# SparkFun_Cryptographic_Co-processor_ATEC.net
KiCad netlist of a schematic drawn in EAGLE
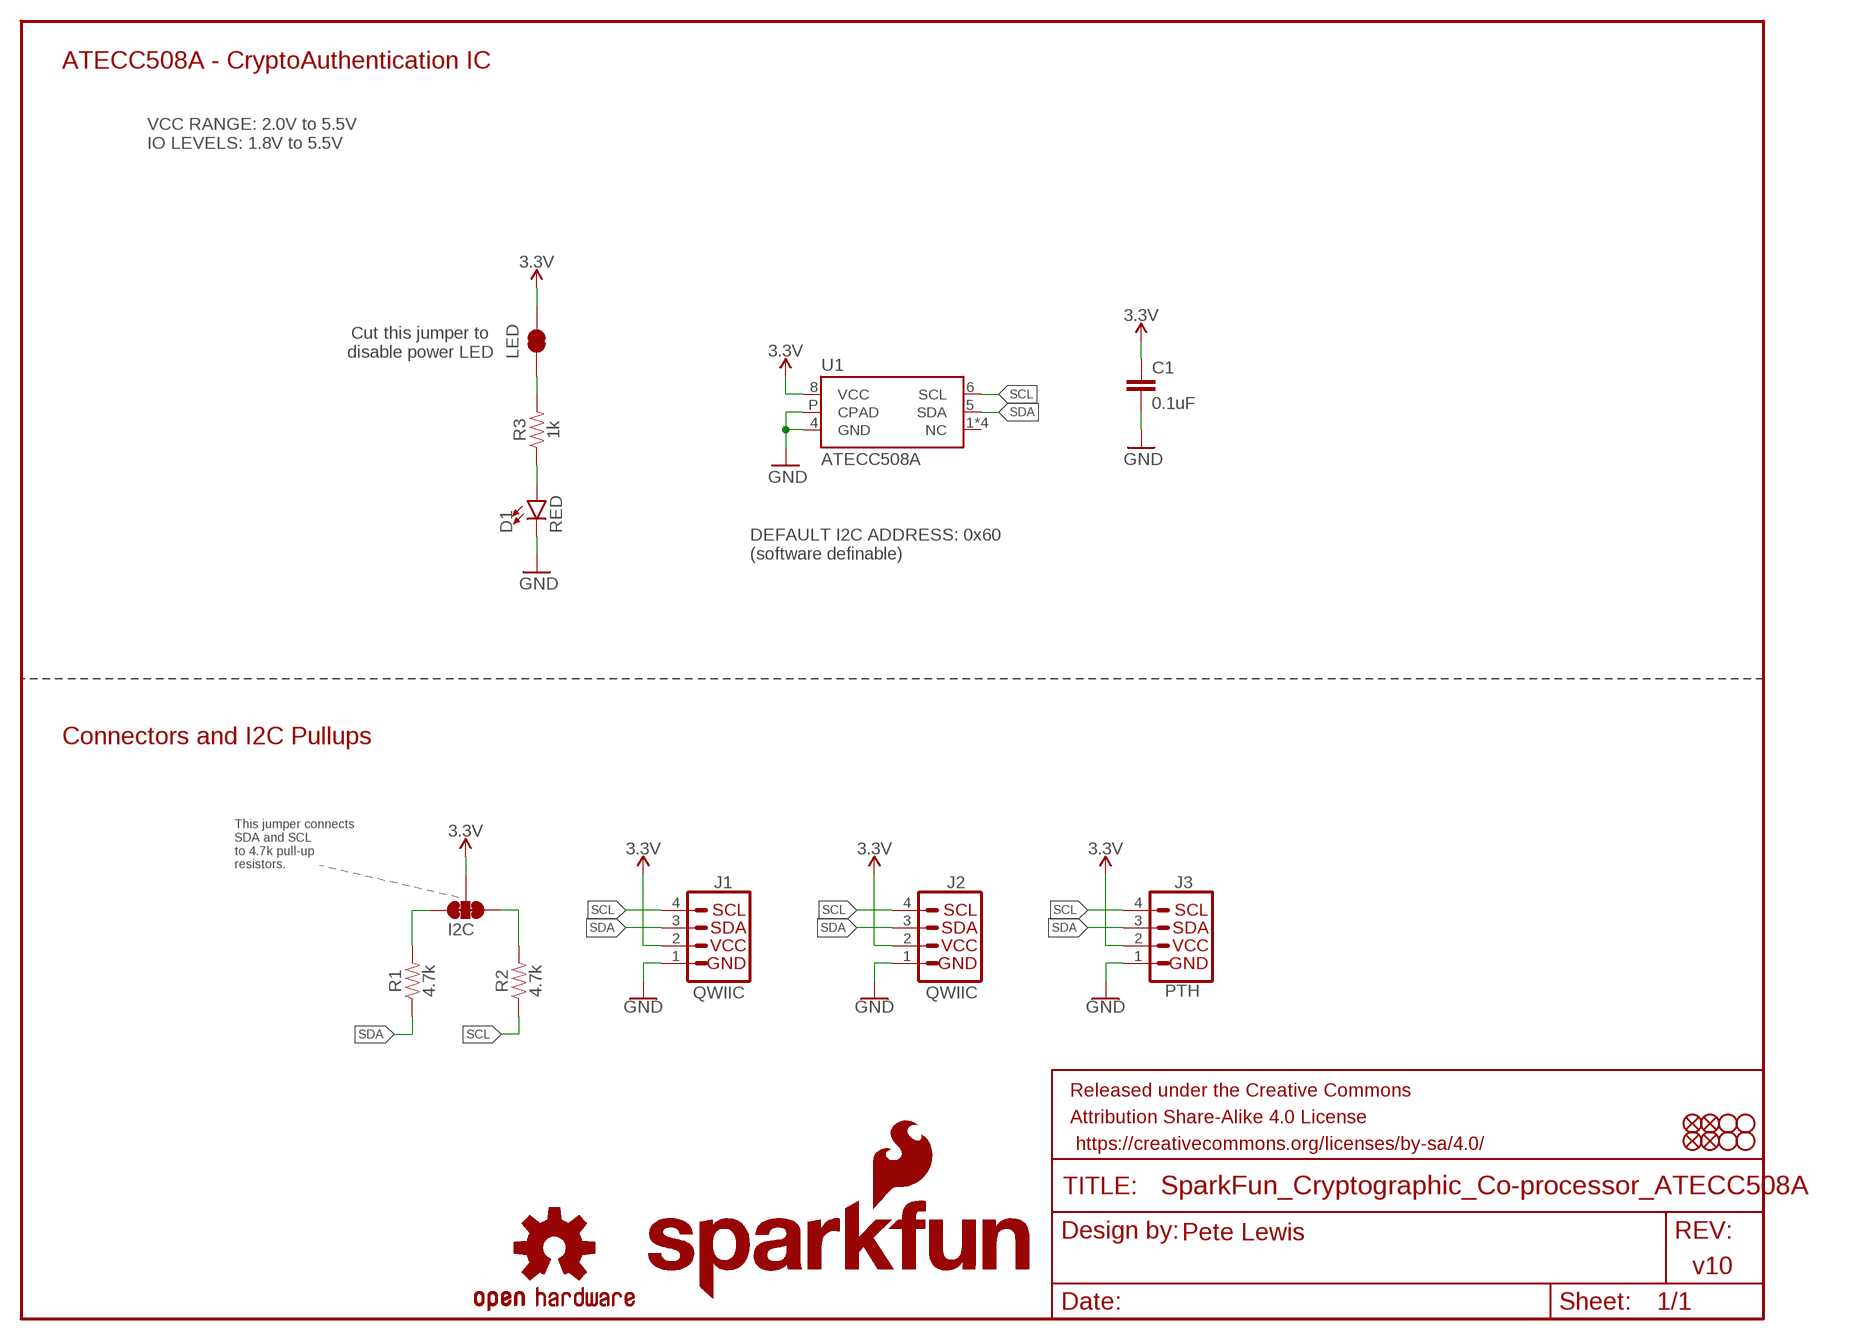
[diagram p0: schematic, sheet 1]

(export (version "E")
  (design (tool "Eeschema 10.0.6"))
  (components
    (comp (ref "C1")
      (value "0.1uF")
      (footprint "eagle-import:0603")
      (libsource (lib "eagle-import") (part "0.1UF-0603-25V-(+80/-20%)"))
    )
    (comp (ref "D1")
      (value "RED")
      (footprint "eagle-import:LED-0603")
      (libsource (lib "eagle-import") (part "LED-RED0603"))
    )
    (comp (ref "FD1")
      (value "FIDUCIAL1X2")
      (footprint "eagle-import:FIDUCIAL-1X2")
      (libsource (lib "eagle-import") (part "FIDUCIAL1X2"))
    )
    (comp (ref "FD2")
      (value "FIDUCIAL1X2")
      (footprint "eagle-import:FIDUCIAL-1X2")
      (libsource (lib "eagle-import") (part "FIDUCIAL1X2"))
    )
    (comp (ref "FD3")
      (value "FIDUCIAL1X2")
      (footprint "eagle-import:FIDUCIAL-1X2")
      (libsource (lib "eagle-import") (part "FIDUCIAL1X2"))
    )
    (comp (ref "FD4")
      (value "FIDUCIAL1X2")
      (footprint "eagle-import:FIDUCIAL-1X2")
      (libsource (lib "eagle-import") (part "FIDUCIAL1X2"))
    )
    (comp (ref "FRAME1")
      (value "FRAME-LETTER")
      (footprint "eagle-import:CREATIVE_COMMONS")
      (libsource (lib "eagle-import") (part "FRAME-LETTER"))
    )
    (comp (ref "H1")
      (value "STAND-OFF")
      (footprint "eagle-import:STAND-OFF")
      (libsource (lib "eagle-import") (part "STAND-OFF"))
    )
    (comp (ref "H2")
      (value "STAND-OFF")
      (footprint "eagle-import:STAND-OFF")
      (libsource (lib "eagle-import") (part "STAND-OFF"))
    )
    (comp (ref "H3")
      (value "STAND-OFF")
      (footprint "eagle-import:STAND-OFF")
      (libsource (lib "eagle-import") (part "STAND-OFF"))
    )
    (comp (ref "H4")
      (value "STAND-OFF")
      (footprint "eagle-import:STAND-OFF")
      (libsource (lib "eagle-import") (part "STAND-OFF"))
    )
    (comp (ref "I2C")
      (value "JUMPER-SMT_3_2-NC_TRACE_SILK")
      (footprint "eagle-import:SMT-JUMPER_3_2-NC_TRACE_SILK")
      (libsource (lib "eagle-import") (part "JUMPER-SMT_3_2-NC_TRACE_SILK"))
    )
    (comp (ref "J1")
      (value "QWIIC")
      (footprint "eagle-import:JST04_1MM_RA")
      (libsource (lib "eagle-import") (part "I2C_STANDARDQWIIC"))
    )
    (comp (ref "J2")
      (value "QWIIC")
      (footprint "eagle-import:JST04_1MM_RA")
      (libsource (lib "eagle-import") (part "I2C_STANDARDQWIIC"))
    )
    (comp (ref "J3")
      (value "PTH")
      (footprint "eagle-import:1X04_NO_SILK")
      (libsource (lib "eagle-import") (part "I2C_STANDARD_NO_SILK"))
    )
    (comp (ref "LED")
      (value "JUMPER-SMT_2_NC_TRACE_SILK")
      (footprint "eagle-import:SMT-JUMPER_2_NC_TRACE_SILK")
      (libsource (lib "eagle-import") (part "JUMPER-SMT_2_NC_TRACE_SILK"))
    )
    (comp (ref "LOGO1")
      (value "SFE_LOGO_NAME_FLAME.1_INCH")
      (footprint "eagle-import:SFE_LOGO_NAME_FLAME_.1")
      (libsource (lib "eagle-import") (part "SFE_LOGO_NAME_FLAME.1_INCH"))
    )
    (comp (ref "LOGO4")
      (value "OSHW-LOGOS")
      (footprint "eagle-import:OSHW-LOGO-S")
      (libsource (lib "eagle-import") (part "OSHW-LOGOS"))
    )
    (comp (ref "R1")
      (value "4.7k")
      (footprint "eagle-import:0603")
      (libsource (lib "eagle-import") (part "4.7KOHM-0603-1/10W-1%"))
    )
    (comp (ref "R2")
      (value "4.7k")
      (footprint "eagle-import:0603")
      (libsource (lib "eagle-import") (part "4.7KOHM-0603-1/10W-1%"))
    )
    (comp (ref "R3")
      (value "1k")
      (footprint "eagle-import:0603")
      (libsource (lib "eagle-import") (part "1KOHM-0603-1/10W-1%"))
    )
    (comp (ref "U1")
      (value "ATECC508A")
      (footprint "eagle-import:UDFN_2X3MM")
      (libsource (lib "eagle-import") (part "ATECC508AUDFN_2X3MM"))
    )
  )
  (nets
    (net (code "1") (name "3.3V") (class "Default")
      (node (ref "C1") (pin "1") (pinfunction "1_1") (pintype "passive"))
      (node (ref "I2C") (pin "2") (pinfunction "2_2") (pintype "passive"))
      (node (ref "J1") (pin "2") (pinfunction "2_2") (pintype "power_in"))
      (node (ref "J2") (pin "2") (pinfunction "2_2") (pintype "power_in"))
      (node (ref "J3") (pin "2") (pinfunction "2_2") (pintype "power_in"))
      (node (ref "LED") (pin "2") (pinfunction "2_2") (pintype "passive"))
      (node (ref "U1") (pin "8") (pinfunction "VCC_8") (pintype "power_in"))
    )
    (net (code "2") (name "GND") (class "Default")
      (node (ref "C1") (pin "2") (pinfunction "2_2") (pintype "passive"))
      (node (ref "D1") (pin "C") (pinfunction "C_C") (pintype "passive"))
      (node (ref "J1") (pin "1") (pinfunction "1_1") (pintype "power_in"))
      (node (ref "J2") (pin "1") (pinfunction "1_1") (pintype "power_in"))
      (node (ref "J3") (pin "1") (pinfunction "1_1") (pintype "power_in"))
      (node (ref "U1") (pin "4") (pinfunction "GND_4") (pintype "power_in"))
      (node (ref "U1") (pin "P") (pinfunction "CPAD_P") (pintype "power_in"))
    )
    (net (code "3") (name "Net-(D1-PadA)") (class "Default")
      (node (ref "D1") (pin "A") (pinfunction "A_A") (pintype "passive"))
      (node (ref "R3") (pin "1") (pinfunction "1_1") (pintype "passive"))
    )
    (net (code "4") (name "Net-(I2C-Pad1)") (class "Default")
      (node (ref "I2C") (pin "1") (pinfunction "1_1") (pintype "passive"))
      (node (ref "R2") (pin "2") (pinfunction "2_2") (pintype "passive"))
    )
    (net (code "5") (name "Net-(I2C-Pad3)") (class "Default")
      (node (ref "I2C") (pin "3") (pinfunction "3_3") (pintype "passive"))
      (node (ref "R1") (pin "2") (pinfunction "2_2") (pintype "passive"))
    )
    (net (code "6") (name "Net-(LED-Pad1)") (class "Default")
      (node (ref "LED") (pin "1") (pinfunction "1_1") (pintype "passive"))
      (node (ref "R3") (pin "2") (pinfunction "2_2") (pintype "passive"))
    )
    (net (code "7") (name "SCL") (class "Default")
      (node (ref "J1") (pin "4") (pinfunction "4_4") (pintype "passive"))
      (node (ref "J2") (pin "4") (pinfunction "4_4") (pintype "passive"))
      (node (ref "J3") (pin "4") (pinfunction "4_4") (pintype "passive"))
      (node (ref "R2") (pin "1") (pinfunction "1_1") (pintype "passive"))
      (node (ref "U1") (pin "6") (pinfunction "SCL_6") (pintype "bidirectional"))
    )
    (net (code "8") (name "SDA") (class "Default")
      (node (ref "J1") (pin "3") (pinfunction "3_3") (pintype "passive"))
      (node (ref "J2") (pin "3") (pinfunction "3_3") (pintype "passive"))
      (node (ref "J3") (pin "3") (pinfunction "3_3") (pintype "passive"))
      (node (ref "R1") (pin "1") (pinfunction "1_1") (pintype "passive"))
      (node (ref "U1") (pin "5") (pinfunction "SDA_5") (pintype "bidirectional"))
    )
    (net (code "9") (name "unconnected-(U1-NC-Pad1)") (class "Default")
      (node (ref "U1") (pin "1") (pinfunction "NC_1") (pintype "no_connect"))
    )
    (net (code "10") (name "unconnected-(U1-NC-Pad2)") (class "Default")
      (node (ref "U1") (pin "2") (pinfunction "NC_2") (pintype "no_connect"))
    )
    (net (code "11") (name "unconnected-(U1-NC-Pad3)") (class "Default")
      (node (ref "U1") (pin "3") (pinfunction "NC_3") (pintype "no_connect"))
    )
    (net (code "12") (name "unconnected-(U1-NC-Pad7)") (class "Default")
      (node (ref "U1") (pin "7") (pinfunction "NC_7") (pintype "no_connect"))
    )
  )
)
